# High_Voltage_H-Bridge_-_Fixed_Copy.net
KiCad netlist of a schematic drawn in Altium Designer
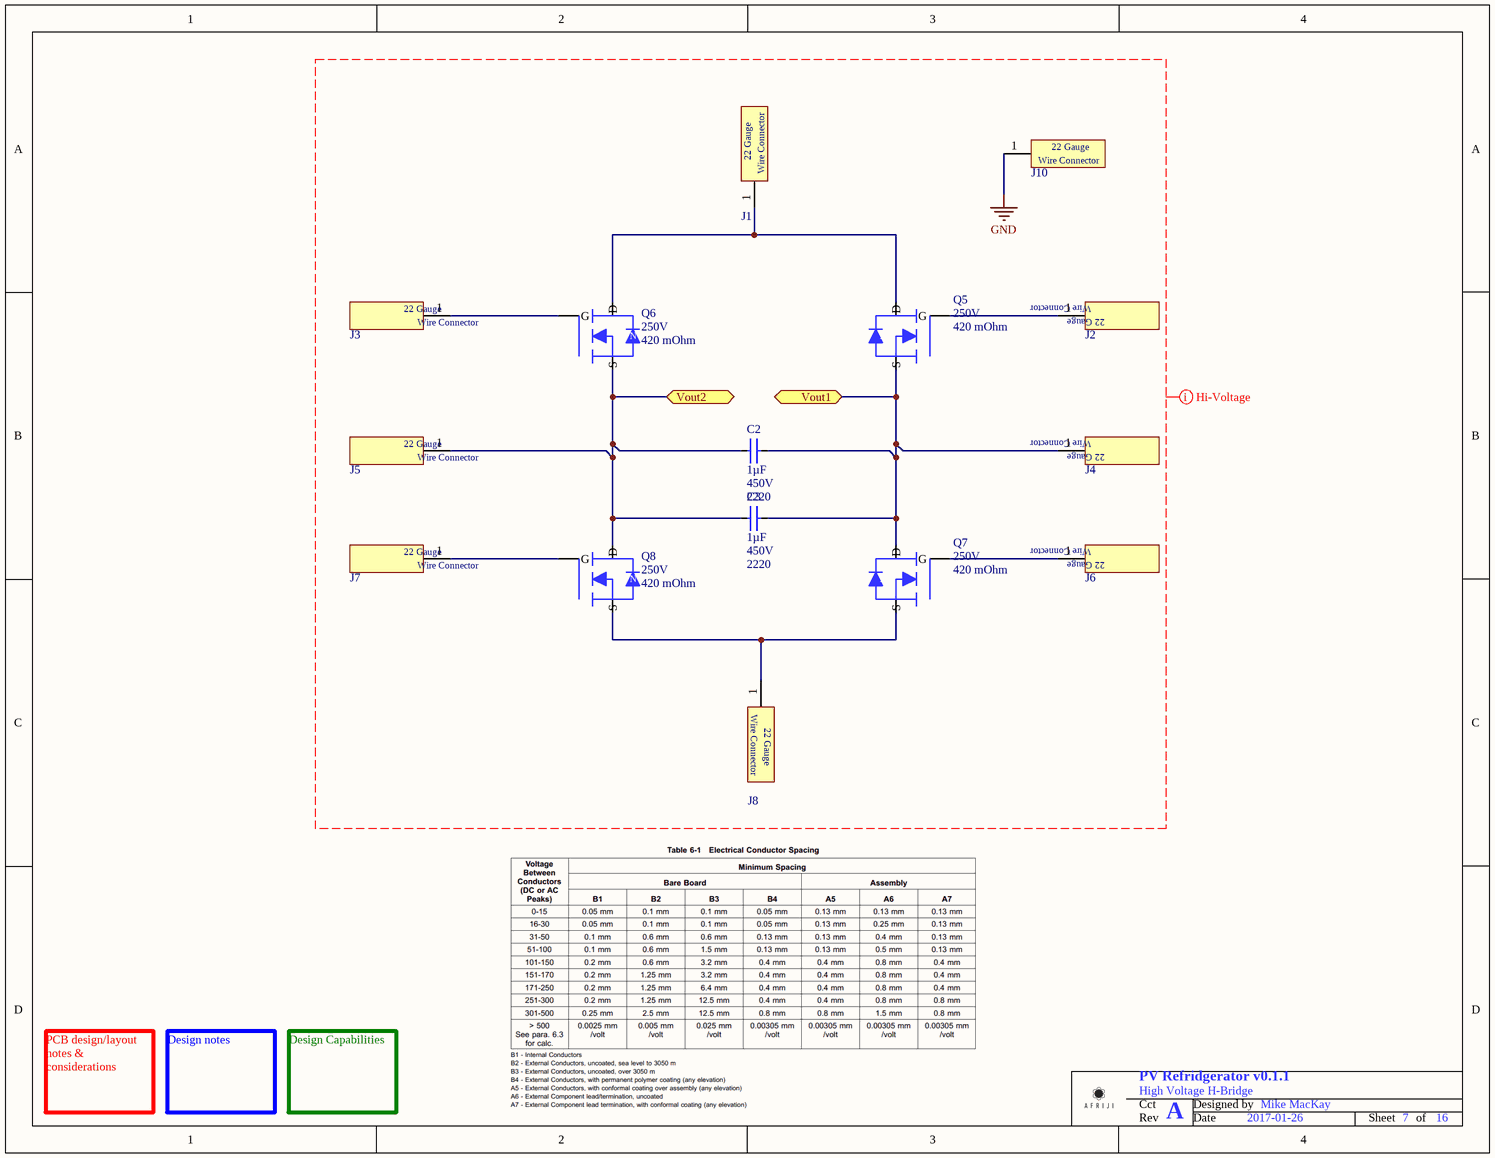
[diagram p0: High Voltage H-Bridge - Fixed Copy.SchDoc]

(export (version "E")
  (design (tool "Eeschema 10.0.6"))
  (components
    (comp (ref "C2")
      (value "1uF 2220 450V")
      (footprint "C2220 - Ceramic")
      (fields
        (field (name "MANUFACTURER") "TDK Corporation")
        (field (name "MANUFACTURER PART NUMBER") "CGA9P4X7T2W105M250KE")
        (field (name "TOLERANCE") "±20%")
        (field (name "CAPACITANCE") "1µF")
        (field (name "VOLTAGE - RATED") "450V")
        (field (name "PACKAGE / CASE") "2220")
      )
      (libsource (lib "Local Library") (part "1uF 2220 450V"))
    )
    (comp (ref "C3")
      (value "1uF 2220 450V")
      (footprint "C2220 - Ceramic")
      (fields
        (field (name "MANUFACTURER") "TDK Corporation")
        (field (name "MANUFACTURER PART NUMBER") "CGA9P4X7T2W105M250KE")
        (field (name "TOLERANCE") "±20%")
        (field (name "CAPACITANCE") "1µF")
        (field (name "VOLTAGE - RATED") "450V")
        (field (name "PACKAGE / CASE") "2220")
      )
      (libsource (lib "Local Library") (part "1uF 2220 450V"))
    )
    (comp (ref "J1")
      (value "15VDC")
      (footprint "1 Pin 22-Gauge Wire Connector")
      (libsource (lib "Personal Library") (part "1 Pin 22-Gauge Wire connector"))
    )
    (comp (ref "J2")
      (value "15VDC")
      (footprint "1 Pin 22-Gauge Wire Connector")
      (libsource (lib "Personal Library") (part "1 Pin 22-Gauge Wire connector"))
    )
    (comp (ref "J3")
      (value "15VDC")
      (footprint "1 Pin 22-Gauge Wire Connector")
      (libsource (lib "") (part "1 Pin 22-Gauge Wire connector_1"))
    )
    (comp (ref "J4")
      (value "15VDC")
      (footprint "1 Pin 22-Gauge Wire Connector")
      (libsource (lib "Personal Library") (part "1 Pin 22-Gauge Wire connector"))
    )
    (comp (ref "J5")
      (value "15VDC")
      (footprint "1 Pin 22-Gauge Wire Connector")
      (libsource (lib "") (part "1 Pin 22-Gauge Wire connector_1"))
    )
    (comp (ref "J6")
      (value "15VDC")
      (footprint "1 Pin 22-Gauge Wire Connector")
      (libsource (lib "Personal Library") (part "1 Pin 22-Gauge Wire connector"))
    )
    (comp (ref "J7")
      (value "15VDC")
      (footprint "1 Pin 22-Gauge Wire Connector")
      (libsource (lib "") (part "1 Pin 22-Gauge Wire connector_1"))
    )
    (comp (ref "J8")
      (value "15VDC")
      (footprint "1 Pin 22-Gauge Wire Connector")
      (libsource (lib "") (part "1 Pin 22-Gauge Wire connector_1"))
    )
    (comp (ref "J10")
      (value "15VDC")
      (footprint "1 Pin 22-Gauge Wire Connector")
      (libsource (lib "") (part "1 Pin 22-Gauge Wire connector_2"))
    )
    (comp (ref "Q5")
      (value "N-MOSFET - 66A/25V")
      (footprint "DPAK")
      (fields
        (field (name "MANUFACTURER") "Fairchild/ON Semiconductor")
        (field (name "MANUFACTURER PART NUMBER") "FQD9N25TM")
        (field (name "DRAIN TO SOURCE VOLTAGE (VDSS)") "250V")
        (field (name "RDS ON (MAX) @ ID, VGS") "420 mOhm")
      )
      (libsource (lib "Personal Library") (part "N-MOSFET - 66A/25V"))
    )
    (comp (ref "Q6")
      (value "N-MOSFET - 66A/25V")
      (footprint "DPAK")
      (fields
        (field (name "MANUFACTURER") "Fairchild/ON Semiconductor")
        (field (name "MANUFACTURER PART NUMBER") "FQD9N25TM")
        (field (name "DRAIN TO SOURCE VOLTAGE (VDSS)") "250V")
        (field (name "RDS ON (MAX) @ ID, VGS") "420 mOhm")
      )
      (libsource (lib "Personal Library") (part "N-MOSFET - 66A/25V"))
    )
    (comp (ref "Q7")
      (value "N-MOSFET - 66A/25V")
      (footprint "DPAK")
      (fields
        (field (name "MANUFACTURER") "Fairchild/ON Semiconductor")
        (field (name "MANUFACTURER PART NUMBER") "FQD9N25TM")
        (field (name "DRAIN TO SOURCE VOLTAGE (VDSS)") "250V")
        (field (name "RDS ON (MAX) @ ID, VGS") "420 mOhm")
      )
      (libsource (lib "Personal Library") (part "N-MOSFET - 66A/25V"))
    )
    (comp (ref "Q8")
      (value "N-MOSFET - 66A/25V")
      (footprint "DPAK")
      (fields
        (field (name "MANUFACTURER") "Fairchild/ON Semiconductor")
        (field (name "MANUFACTURER PART NUMBER") "FQD9N25TM")
        (field (name "DRAIN TO SOURCE VOLTAGE (VDSS)") "250V")
        (field (name "RDS ON (MAX) @ ID, VGS") "420 mOhm")
      )
      (libsource (lib "Personal Library") (part "N-MOSFET - 66A/25V"))
    )
  )
  (nets
    (net (code "1") (name "/Vout1") (class "Default")
      (node (ref "C2") (pin "1") (pinfunction "1_1") (pintype "passive"))
      (node (ref "C3") (pin "1") (pinfunction "1_1") (pintype "passive"))
      (node (ref "J4") (pin "1") (pinfunction "1_1") (pintype "passive"))
      (node (ref "Q5") (pin "3") (pinfunction "S_3") (pintype "passive"))
      (node (ref "Q7") (pin "2") (pinfunction "D_2") (pintype "passive"))
    )
    (net (code "2") (name "/Vout2") (class "Default")
      (node (ref "C2") (pin "2") (pinfunction "2_2") (pintype "passive"))
      (node (ref "C3") (pin "2") (pinfunction "2_2") (pintype "passive"))
      (node (ref "J5") (pin "1") (pinfunction "1_1") (pintype "passive"))
      (node (ref "Q6") (pin "3") (pinfunction "S_3") (pintype "passive"))
      (node (ref "Q8") (pin "2") (pinfunction "D_2") (pintype "passive"))
    )
    (net (code "3") (name "GND") (class "Default")
      (node (ref "J10") (pin "1") (pinfunction "1_1") (pintype "passive"))
    )
    (net (code "4") (name "Net-(Q5-D)") (class "Default")
      (node (ref "J1") (pin "1") (pinfunction "1_1") (pintype "passive"))
      (node (ref "Q5") (pin "2") (pinfunction "D_2") (pintype "passive"))
      (node (ref "Q6") (pin "2") (pinfunction "D_2") (pintype "passive"))
    )
    (net (code "5") (name "Net-(Q5-G)") (class "Default")
      (node (ref "J2") (pin "1") (pinfunction "1_1") (pintype "passive"))
      (node (ref "Q5") (pin "1") (pinfunction "G_1") (pintype "passive"))
    )
    (net (code "6") (name "Net-(Q6-G)") (class "Default")
      (node (ref "J3") (pin "1") (pinfunction "1_1") (pintype "passive"))
      (node (ref "Q6") (pin "1") (pinfunction "G_1") (pintype "passive"))
    )
    (net (code "7") (name "Net-(Q7-G)") (class "Default")
      (node (ref "J6") (pin "1") (pinfunction "1_1") (pintype "passive"))
      (node (ref "Q7") (pin "1") (pinfunction "G_1") (pintype "passive"))
    )
    (net (code "8") (name "Net-(Q7-S)") (class "Default")
      (node (ref "J8") (pin "1") (pinfunction "1_1") (pintype "passive"))
      (node (ref "Q7") (pin "3") (pinfunction "S_3") (pintype "passive"))
      (node (ref "Q8") (pin "3") (pinfunction "S_3") (pintype "passive"))
    )
    (net (code "9") (name "Net-(Q8-G)") (class "Default")
      (node (ref "J7") (pin "1") (pinfunction "1_1") (pintype "passive"))
      (node (ref "Q8") (pin "1") (pinfunction "G_1") (pintype "passive"))
    )
  )
)
